# Connector_Sheet.net
KiCad netlist of a schematic drawn in Altium Designer
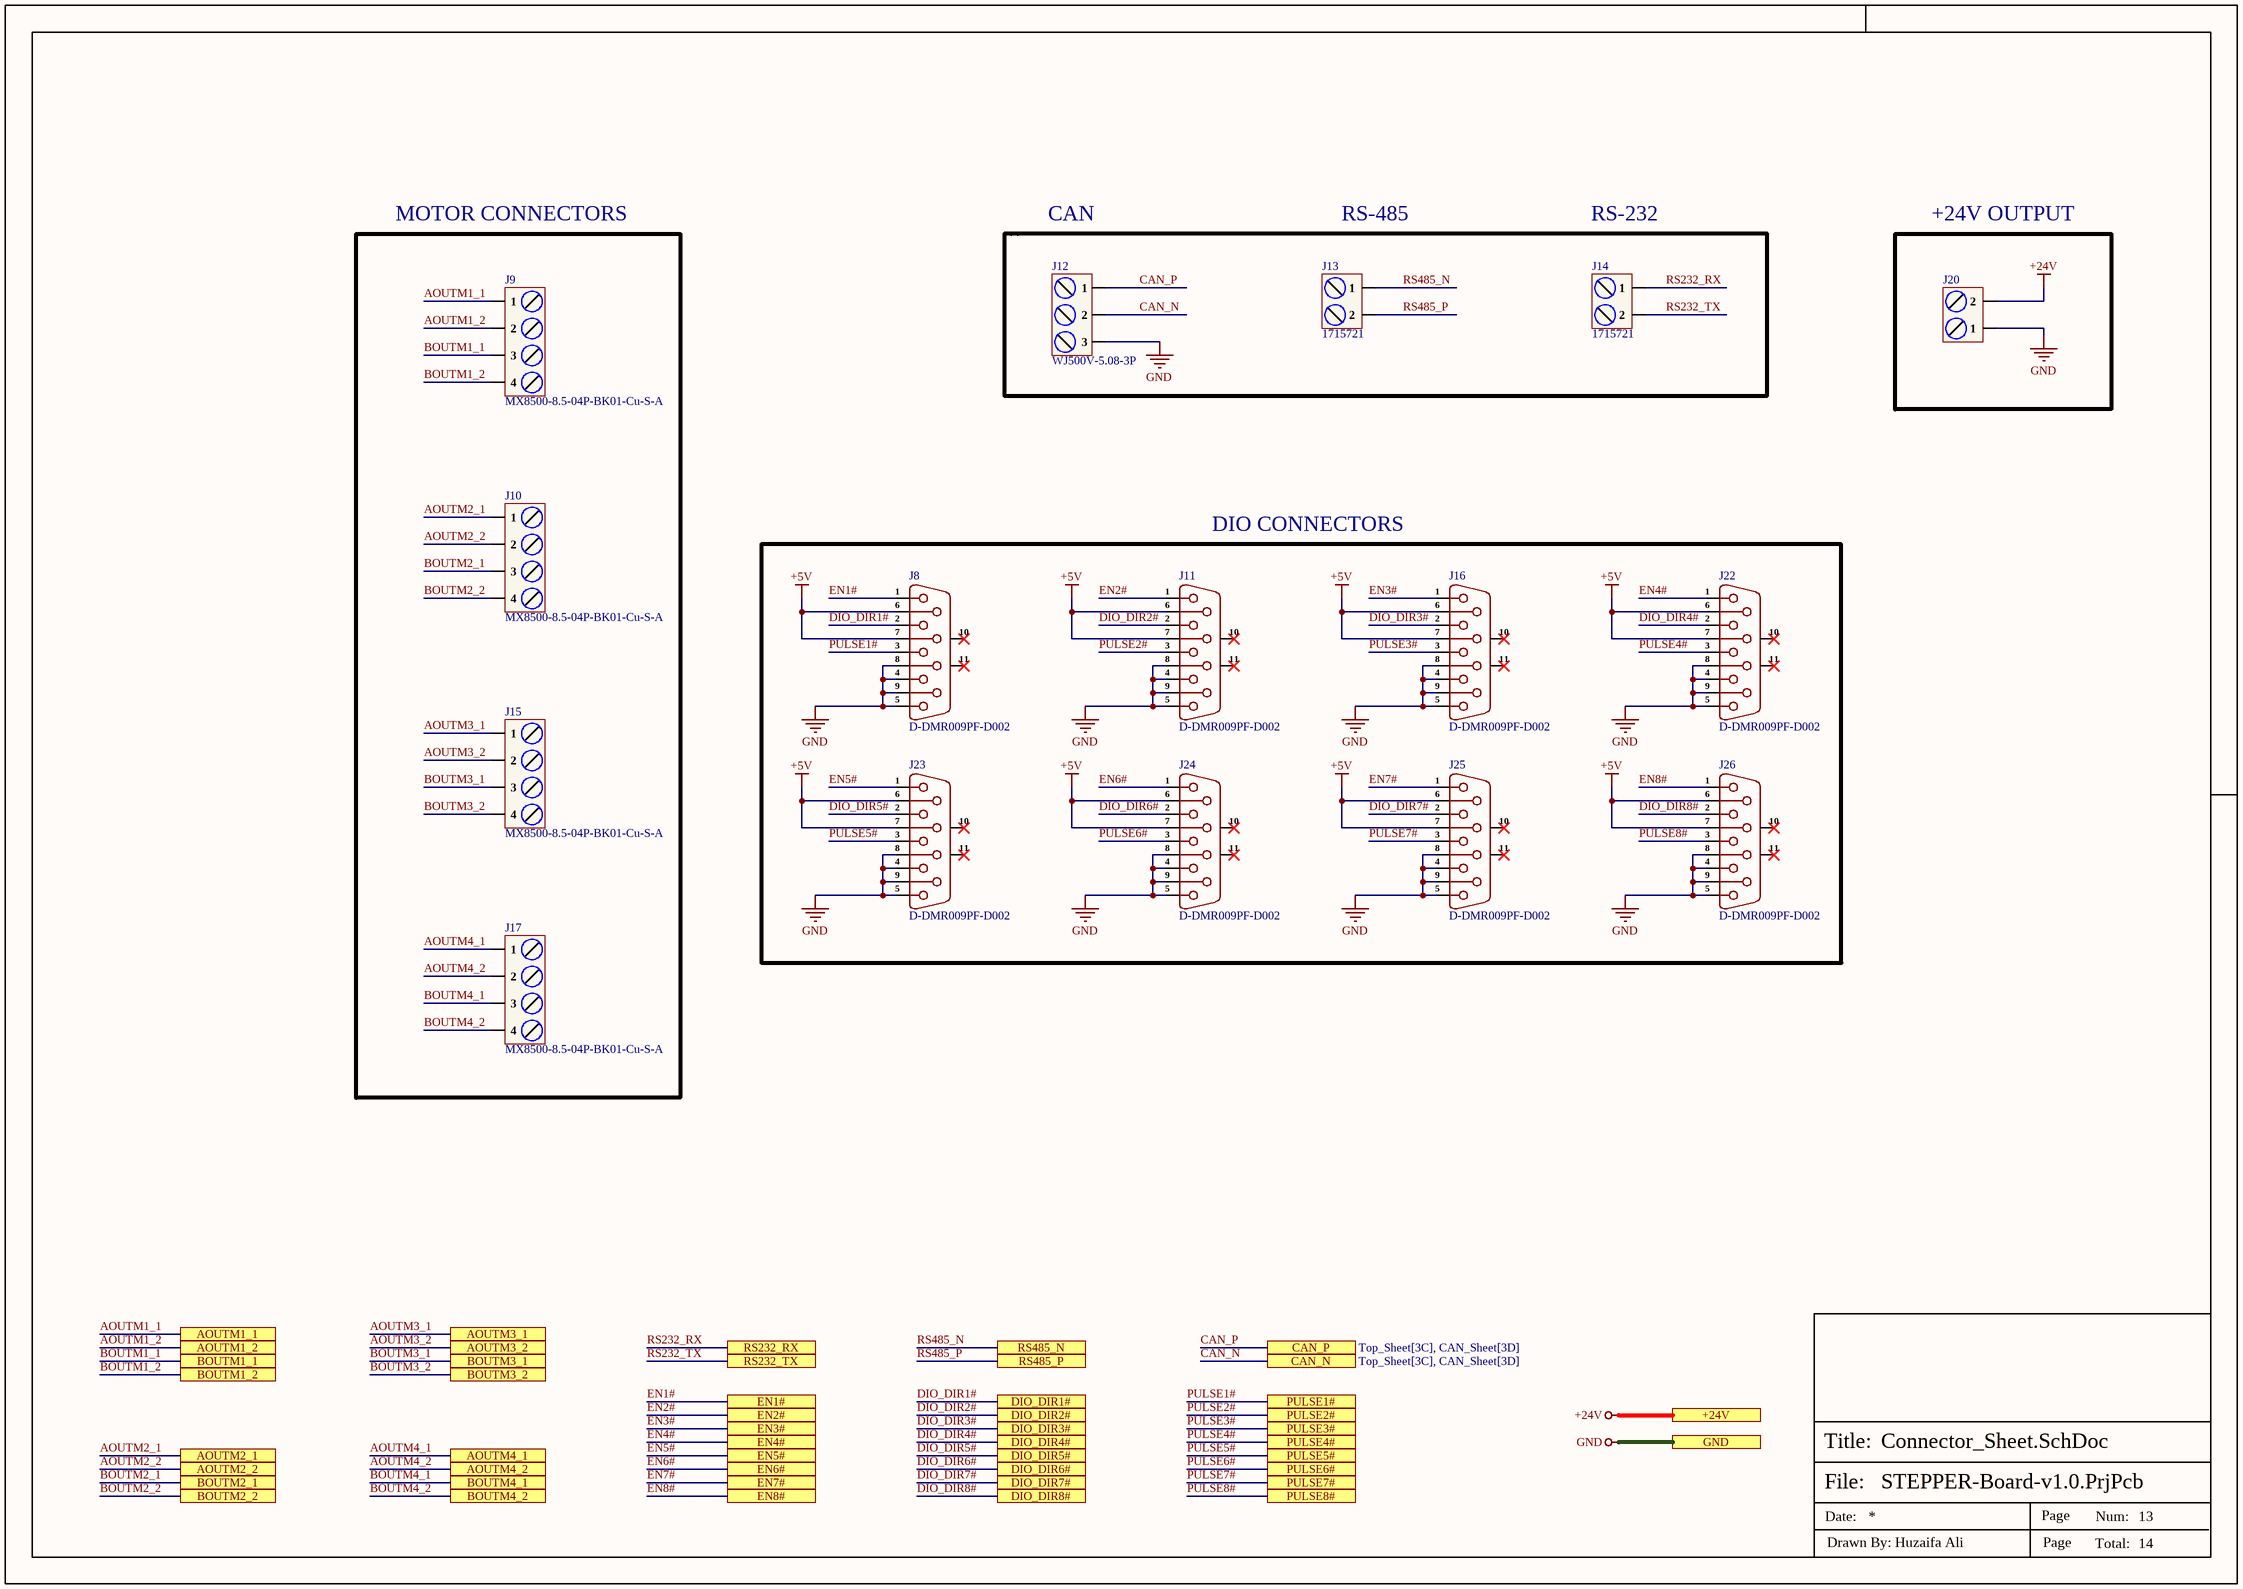
[diagram p0: Connector_Sheet.SchDoc]

(export (version "E")
  (design (tool "Eeschema 10.0.6"))
  (components
    (comp (ref "J8")
      (value "D-DMR009PF-D002")
      (footprint "D-DMR009PF-D002")
      (description "9P Female D-Sub Right-Angle 2 3A -50℃~+105℃ Push-Pull D-Sub / VGA connector ROHS")
      (fields (field (name "MANUFACTURER") "Ckmtw") (field (name "LCSC PART NUMBER") "C141882"))
      (libsource (lib "eSpark Libraries") (part "D-DMR009PF-D002"))
    )
    (comp (ref "J9")
      (value "MX8500-8.5-04P-BK01-Cu-S-A")
      (footprint "MX8500-8.5-04P-BK01-Cu-S-A")
      (fields (field (name "MANUFACTURER") "MAX") (field (name "LCSC PART NUMBER") "C5188508"))
      (libsource (lib "eSpark Libraries") (part "MX8500-8.5-04P-BK01-Cu-S-A"))
    )
    (comp (ref "J10")
      (value "MX8500-8.5-04P-BK01-Cu-S-A")
      (footprint "MX8500-8.5-04P-BK01-Cu-S-A")
      (fields (field (name "MANUFACTURER") "MAX") (field (name "LCSC PART NUMBER") "C5188508"))
      (libsource (lib "eSpark Libraries") (part "MX8500-8.5-04P-BK01-Cu-S-A"))
    )
    (comp (ref "J11")
      (value "D-DMR009PF-D002")
      (footprint "D-DMR009PF-D002")
      (description "9P Female D-Sub Right-Angle 2 3A -50℃~+105℃ Push-Pull D-Sub / VGA connector ROHS")
      (fields (field (name "MANUFACTURER") "Ckmtw") (field (name "LCSC PART NUMBER") "C141882"))
      (libsource (lib "eSpark Libraries") (part "D-DMR009PF-D002"))
    )
    (comp (ref "J12")
      (value "WJ500V-5.08-3P")
      (footprint "WJ500V-5.08-3P")
      (fields (field (name "MANUFACTURER") "Ningbo Kangnex Elec") (field (name "LCSC PART NUMBER") "C72334"))
      (libsource (lib "eSpark Libraries") (part "WJ500V-5.08-3P"))
    )
    (comp (ref "J13")
      (value "1715721")
      (footprint "1715721")
      (description "TERM BLK 2P SIDE ENT 5.08MM PCB")
      (fields (field (name "MANUFACTURER") "Phoenix Contact"))
      (libsource (lib "eSpark Libraries") (part "1715721"))
    )
    (comp (ref "J14")
      (value "1715721")
      (footprint "1715721")
      (description "TERM BLK 2P SIDE ENT 5.08MM PCB")
      (fields (field (name "MANUFACTURER") "Phoenix Contact"))
      (libsource (lib "eSpark Libraries") (part "1715721"))
    )
    (comp (ref "J15")
      (value "MX8500-8.5-04P-BK01-Cu-S-A")
      (footprint "MX8500-8.5-04P-BK01-Cu-S-A")
      (fields (field (name "MANUFACTURER") "MAX") (field (name "LCSC PART NUMBER") "C5188508"))
      (libsource (lib "eSpark Libraries") (part "MX8500-8.5-04P-BK01-Cu-S-A"))
    )
    (comp (ref "J16")
      (value "D-DMR009PF-D002")
      (footprint "D-DMR009PF-D002")
      (description "9P Female D-Sub Right-Angle 2 3A -50℃~+105℃ Push-Pull D-Sub / VGA connector ROHS")
      (fields (field (name "MANUFACTURER") "Ckmtw") (field (name "LCSC PART NUMBER") "C141882"))
      (libsource (lib "eSpark Libraries") (part "D-DMR009PF-D002"))
    )
    (comp (ref "J17")
      (value "MX8500-8.5-04P-BK01-Cu-S-A")
      (footprint "MX8500-8.5-04P-BK01-Cu-S-A")
      (fields (field (name "MANUFACTURER") "MAX") (field (name "LCSC PART NUMBER") "C5188508"))
      (libsource (lib "eSpark Libraries") (part "MX8500-8.5-04P-BK01-Cu-S-A"))
    )
    (comp (ref "J20")
      (value "MXHB9500-9.5-02P-BK01-Cu-S-A")
      (footprint "MXHB9500-9.5-02P-BK01-Cu-S-A")
      (fields (field (name "MANUFACTURER") "MAX") (field (name "LCSC PART NUMBER") "C7542168"))
      (libsource (lib "eSpark Libraries") (part "MXHB9500-9.5-02P-BK01-Cu-S-A"))
    )
    (comp (ref "J22")
      (value "D-DMR009PF-D002")
      (footprint "D-DMR009PF-D002")
      (description "9P Female D-Sub Right-Angle 2 3A -50℃~+105℃ Push-Pull D-Sub / VGA connector ROHS")
      (fields (field (name "MANUFACTURER") "Ckmtw") (field (name "LCSC PART NUMBER") "C141882"))
      (libsource (lib "eSpark Libraries") (part "D-DMR009PF-D002"))
    )
    (comp (ref "J23")
      (value "D-DMR009PF-D002")
      (footprint "D-DMR009PF-D002")
      (description "9P Female D-Sub Right-Angle 2 3A -50℃~+105℃ Push-Pull D-Sub / VGA connector ROHS")
      (fields (field (name "MANUFACTURER") "Ckmtw") (field (name "LCSC PART NUMBER") "C141882"))
      (libsource (lib "eSpark Libraries") (part "D-DMR009PF-D002"))
    )
    (comp (ref "J24")
      (value "D-DMR009PF-D002")
      (footprint "D-DMR009PF-D002")
      (description "9P Female D-Sub Right-Angle 2 3A -50℃~+105℃ Push-Pull D-Sub / VGA connector ROHS")
      (fields (field (name "MANUFACTURER") "Ckmtw") (field (name "LCSC PART NUMBER") "C141882"))
      (libsource (lib "eSpark Libraries") (part "D-DMR009PF-D002"))
    )
    (comp (ref "J25")
      (value "D-DMR009PF-D002")
      (footprint "D-DMR009PF-D002")
      (description "9P Female D-Sub Right-Angle 2 3A -50℃~+105℃ Push-Pull D-Sub / VGA connector ROHS")
      (fields (field (name "MANUFACTURER") "Ckmtw") (field (name "LCSC PART NUMBER") "C141882"))
      (libsource (lib "eSpark Libraries") (part "D-DMR009PF-D002"))
    )
    (comp (ref "J26")
      (value "D-DMR009PF-D002")
      (footprint "D-DMR009PF-D002")
      (description "9P Female D-Sub Right-Angle 2 3A -50℃~+105℃ Push-Pull D-Sub / VGA connector ROHS")
      (fields (field (name "MANUFACTURER") "Ckmtw") (field (name "LCSC PART NUMBER") "C141882"))
      (libsource (lib "eSpark Libraries") (part "D-DMR009PF-D002"))
    )
  )
  (nets
    (net (code "1") (name "+5V") (class "Default")
      (node (ref "J11") (pin "6") (pinfunction "6_6") (pintype "passive"))
      (node (ref "J11") (pin "7") (pinfunction "7_7") (pintype "passive"))
      (node (ref "J16") (pin "6") (pinfunction "6_6") (pintype "passive"))
      (node (ref "J16") (pin "7") (pinfunction "7_7") (pintype "passive"))
      (node (ref "J22") (pin "6") (pinfunction "6_6") (pintype "passive"))
      (node (ref "J22") (pin "7") (pinfunction "7_7") (pintype "passive"))
      (node (ref "J23") (pin "6") (pinfunction "6_6") (pintype "passive"))
      (node (ref "J23") (pin "7") (pinfunction "7_7") (pintype "passive"))
      (node (ref "J24") (pin "6") (pinfunction "6_6") (pintype "passive"))
      (node (ref "J24") (pin "7") (pinfunction "7_7") (pintype "passive"))
      (node (ref "J25") (pin "6") (pinfunction "6_6") (pintype "passive"))
      (node (ref "J25") (pin "7") (pinfunction "7_7") (pintype "passive"))
      (node (ref "J26") (pin "6") (pinfunction "6_6") (pintype "passive"))
      (node (ref "J26") (pin "7") (pinfunction "7_7") (pintype "passive"))
      (node (ref "J8") (pin "6") (pinfunction "6_6") (pintype "passive"))
      (node (ref "J8") (pin "7") (pinfunction "7_7") (pintype "passive"))
    )
    (net (code "2") (name "+24V") (class "Default")
      (node (ref "J20") (pin "2") (pinfunction "2_2") (pintype "passive"))
    )
    (net (code "3") (name "/AOUTM1_1") (class "Default")
      (node (ref "J9") (pin "1") (pinfunction "1_1") (pintype "passive"))
    )
    (net (code "4") (name "/AOUTM1_2") (class "Default")
      (node (ref "J9") (pin "2") (pinfunction "2_2") (pintype "passive"))
    )
    (net (code "5") (name "/AOUTM2_1") (class "Default")
      (node (ref "J10") (pin "1") (pinfunction "1_1") (pintype "passive"))
    )
    (net (code "6") (name "/AOUTM2_2") (class "Default")
      (node (ref "J10") (pin "2") (pinfunction "2_2") (pintype "passive"))
    )
    (net (code "7") (name "/AOUTM3_1") (class "Default")
      (node (ref "J15") (pin "1") (pinfunction "1_1") (pintype "passive"))
    )
    (net (code "8") (name "/AOUTM3_2") (class "Default")
      (node (ref "J15") (pin "2") (pinfunction "2_2") (pintype "passive"))
    )
    (net (code "9") (name "/AOUTM4_1") (class "Default")
      (node (ref "J17") (pin "1") (pinfunction "1_1") (pintype "passive"))
    )
    (net (code "10") (name "/AOUTM4_2") (class "Default")
      (node (ref "J17") (pin "2") (pinfunction "2_2") (pintype "passive"))
    )
    (net (code "11") (name "/BOUTM1_1") (class "Default")
      (node (ref "J9") (pin "3") (pinfunction "3_3") (pintype "passive"))
    )
    (net (code "12") (name "/BOUTM1_2") (class "Default")
      (node (ref "J9") (pin "4") (pinfunction "4_4") (pintype "passive"))
    )
    (net (code "13") (name "/BOUTM2_1") (class "Default")
      (node (ref "J10") (pin "3") (pinfunction "3_3") (pintype "passive"))
    )
    (net (code "14") (name "/BOUTM2_2") (class "Default")
      (node (ref "J10") (pin "4") (pinfunction "4_4") (pintype "passive"))
    )
    (net (code "15") (name "/BOUTM3_1") (class "Default")
      (node (ref "J15") (pin "3") (pinfunction "3_3") (pintype "passive"))
    )
    (net (code "16") (name "/BOUTM3_2") (class "Default")
      (node (ref "J15") (pin "4") (pinfunction "4_4") (pintype "passive"))
    )
    (net (code "17") (name "/BOUTM4_1") (class "Default")
      (node (ref "J17") (pin "3") (pinfunction "3_3") (pintype "passive"))
    )
    (net (code "18") (name "/BOUTM4_2") (class "Default")
      (node (ref "J17") (pin "4") (pinfunction "4_4") (pintype "passive"))
    )
    (net (code "19") (name "/CAN_N") (class "Default")
      (node (ref "J12") (pin "2") (pinfunction "2_2") (pintype "passive"))
    )
    (net (code "20") (name "/CAN_P") (class "Default")
      (node (ref "J12") (pin "1") (pinfunction "1_1") (pintype "passive"))
    )
    (net (code "21") (name "/DIO_DIR1#") (class "Default")
      (node (ref "J8") (pin "2") (pinfunction "2_2") (pintype "passive"))
    )
    (net (code "22") (name "/DIO_DIR2#") (class "Default")
      (node (ref "J11") (pin "2") (pinfunction "2_2") (pintype "passive"))
    )
    (net (code "23") (name "/DIO_DIR3#") (class "Default")
      (node (ref "J16") (pin "2") (pinfunction "2_2") (pintype "passive"))
    )
    (net (code "24") (name "/DIO_DIR4#") (class "Default")
      (node (ref "J22") (pin "2") (pinfunction "2_2") (pintype "passive"))
    )
    (net (code "25") (name "/DIO_DIR5#") (class "Default")
      (node (ref "J23") (pin "2") (pinfunction "2_2") (pintype "passive"))
    )
    (net (code "26") (name "/DIO_DIR6#") (class "Default")
      (node (ref "J24") (pin "2") (pinfunction "2_2") (pintype "passive"))
    )
    (net (code "27") (name "/DIO_DIR7#") (class "Default")
      (node (ref "J25") (pin "2") (pinfunction "2_2") (pintype "passive"))
    )
    (net (code "28") (name "/DIO_DIR8#") (class "Default")
      (node (ref "J26") (pin "2") (pinfunction "2_2") (pintype "passive"))
    )
    (net (code "29") (name "/EN1#") (class "Default")
      (node (ref "J8") (pin "1") (pinfunction "1_1") (pintype "passive"))
    )
    (net (code "30") (name "/EN2#") (class "Default")
      (node (ref "J11") (pin "1") (pinfunction "1_1") (pintype "passive"))
    )
    (net (code "31") (name "/EN3#") (class "Default")
      (node (ref "J16") (pin "1") (pinfunction "1_1") (pintype "passive"))
    )
    (net (code "32") (name "/EN4#") (class "Default")
      (node (ref "J22") (pin "1") (pinfunction "1_1") (pintype "passive"))
    )
    (net (code "33") (name "/EN5#") (class "Default")
      (node (ref "J23") (pin "1") (pinfunction "1_1") (pintype "passive"))
    )
    (net (code "34") (name "/EN6#") (class "Default")
      (node (ref "J24") (pin "1") (pinfunction "1_1") (pintype "passive"))
    )
    (net (code "35") (name "/EN7#") (class "Default")
      (node (ref "J25") (pin "1") (pinfunction "1_1") (pintype "passive"))
    )
    (net (code "36") (name "/EN8#") (class "Default")
      (node (ref "J26") (pin "1") (pinfunction "1_1") (pintype "passive"))
    )
    (net (code "37") (name "/PULSE1#") (class "Default")
      (node (ref "J8") (pin "3") (pinfunction "3_3") (pintype "passive"))
    )
    (net (code "38") (name "/PULSE2#") (class "Default")
      (node (ref "J11") (pin "3") (pinfunction "3_3") (pintype "passive"))
    )
    (net (code "39") (name "/PULSE3#") (class "Default")
      (node (ref "J16") (pin "3") (pinfunction "3_3") (pintype "passive"))
    )
    (net (code "40") (name "/PULSE4#") (class "Default")
      (node (ref "J22") (pin "3") (pinfunction "3_3") (pintype "passive"))
    )
    (net (code "41") (name "/PULSE5#") (class "Default")
      (node (ref "J23") (pin "3") (pinfunction "3_3") (pintype "passive"))
    )
    (net (code "42") (name "/PULSE6#") (class "Default")
      (node (ref "J24") (pin "3") (pinfunction "3_3") (pintype "passive"))
    )
    (net (code "43") (name "/PULSE7#") (class "Default")
      (node (ref "J25") (pin "3") (pinfunction "3_3") (pintype "passive"))
    )
    (net (code "44") (name "/PULSE8#") (class "Default")
      (node (ref "J26") (pin "3") (pinfunction "3_3") (pintype "passive"))
    )
    (net (code "45") (name "/RS232_RX") (class "Default")
      (node (ref "J14") (pin "1") (pinfunction "1_1") (pintype "passive"))
    )
    (net (code "46") (name "/RS232_TX") (class "Default")
      (node (ref "J14") (pin "2") (pinfunction "2_2") (pintype "passive"))
    )
    (net (code "47") (name "/RS485_N") (class "Default")
      (node (ref "J13") (pin "1") (pinfunction "1_1") (pintype "passive"))
    )
    (net (code "48") (name "/RS485_P") (class "Default")
      (node (ref "J13") (pin "2") (pinfunction "2_2") (pintype "passive"))
    )
    (net (code "49") (name "GND") (class "Default")
      (node (ref "J11") (pin "4") (pinfunction "4_4") (pintype "passive"))
      (node (ref "J11") (pin "5") (pinfunction "5_5") (pintype "passive"))
      (node (ref "J11") (pin "8") (pinfunction "8_8") (pintype "passive"))
      (node (ref "J11") (pin "9") (pinfunction "9_9") (pintype "passive"))
      (node (ref "J12") (pin "3") (pinfunction "3_3") (pintype "passive"))
      (node (ref "J16") (pin "4") (pinfunction "4_4") (pintype "passive"))
      (node (ref "J16") (pin "5") (pinfunction "5_5") (pintype "passive"))
      (node (ref "J16") (pin "8") (pinfunction "8_8") (pintype "passive"))
      (node (ref "J16") (pin "9") (pinfunction "9_9") (pintype "passive"))
      (node (ref "J20") (pin "1") (pinfunction "1_1") (pintype "passive"))
      (node (ref "J22") (pin "4") (pinfunction "4_4") (pintype "passive"))
      (node (ref "J22") (pin "5") (pinfunction "5_5") (pintype "passive"))
      (node (ref "J22") (pin "8") (pinfunction "8_8") (pintype "passive"))
      (node (ref "J22") (pin "9") (pinfunction "9_9") (pintype "passive"))
      (node (ref "J23") (pin "4") (pinfunction "4_4") (pintype "passive"))
      (node (ref "J23") (pin "5") (pinfunction "5_5") (pintype "passive"))
      (node (ref "J23") (pin "8") (pinfunction "8_8") (pintype "passive"))
      (node (ref "J23") (pin "9") (pinfunction "9_9") (pintype "passive"))
      (node (ref "J24") (pin "4") (pinfunction "4_4") (pintype "passive"))
      (node (ref "J24") (pin "5") (pinfunction "5_5") (pintype "passive"))
      (node (ref "J24") (pin "8") (pinfunction "8_8") (pintype "passive"))
      (node (ref "J24") (pin "9") (pinfunction "9_9") (pintype "passive"))
      (node (ref "J25") (pin "4") (pinfunction "4_4") (pintype "passive"))
      (node (ref "J25") (pin "5") (pinfunction "5_5") (pintype "passive"))
      (node (ref "J25") (pin "8") (pinfunction "8_8") (pintype "passive"))
      (node (ref "J25") (pin "9") (pinfunction "9_9") (pintype "passive"))
      (node (ref "J26") (pin "4") (pinfunction "4_4") (pintype "passive"))
      (node (ref "J26") (pin "5") (pinfunction "5_5") (pintype "passive"))
      (node (ref "J26") (pin "8") (pinfunction "8_8") (pintype "passive"))
      (node (ref "J26") (pin "9") (pinfunction "9_9") (pintype "passive"))
      (node (ref "J8") (pin "4") (pinfunction "4_4") (pintype "passive"))
      (node (ref "J8") (pin "5") (pinfunction "5_5") (pintype "passive"))
      (node (ref "J8") (pin "8") (pinfunction "8_8") (pintype "passive"))
      (node (ref "J8") (pin "9") (pinfunction "9_9") (pintype "passive"))
    )
    (net (code "50") (name "unconnected-(J8-MH1-Pad10)") (class "Default")
      (node (ref "J8") (pin "10") (pinfunction "MH1_10") (pintype "passive+no_connect"))
    )
    (net (code "51") (name "unconnected-(J8-MH2-Pad11)") (class "Default")
      (node (ref "J8") (pin "11") (pinfunction "MH2_11") (pintype "passive+no_connect"))
    )
    (net (code "52") (name "unconnected-(J11-MH1-Pad10)") (class "Default")
      (node (ref "J11") (pin "10") (pinfunction "MH1_10") (pintype "passive+no_connect"))
    )
    (net (code "53") (name "unconnected-(J11-MH2-Pad11)") (class "Default")
      (node (ref "J11") (pin "11") (pinfunction "MH2_11") (pintype "passive+no_connect"))
    )
    (net (code "54") (name "unconnected-(J16-MH1-Pad10)") (class "Default")
      (node (ref "J16") (pin "10") (pinfunction "MH1_10") (pintype "passive+no_connect"))
    )
    (net (code "55") (name "unconnected-(J16-MH2-Pad11)") (class "Default")
      (node (ref "J16") (pin "11") (pinfunction "MH2_11") (pintype "passive+no_connect"))
    )
    (net (code "56") (name "unconnected-(J22-MH1-Pad10)") (class "Default")
      (node (ref "J22") (pin "10") (pinfunction "MH1_10") (pintype "passive+no_connect"))
    )
    (net (code "57") (name "unconnected-(J22-MH2-Pad11)") (class "Default")
      (node (ref "J22") (pin "11") (pinfunction "MH2_11") (pintype "passive+no_connect"))
    )
    (net (code "58") (name "unconnected-(J23-MH1-Pad10)") (class "Default")
      (node (ref "J23") (pin "10") (pinfunction "MH1_10") (pintype "passive+no_connect"))
    )
    (net (code "59") (name "unconnected-(J23-MH2-Pad11)") (class "Default")
      (node (ref "J23") (pin "11") (pinfunction "MH2_11") (pintype "passive+no_connect"))
    )
    (net (code "60") (name "unconnected-(J24-MH1-Pad10)") (class "Default")
      (node (ref "J24") (pin "10") (pinfunction "MH1_10") (pintype "passive+no_connect"))
    )
    (net (code "61") (name "unconnected-(J24-MH2-Pad11)") (class "Default")
      (node (ref "J24") (pin "11") (pinfunction "MH2_11") (pintype "passive+no_connect"))
    )
    (net (code "62") (name "unconnected-(J25-MH1-Pad10)") (class "Default")
      (node (ref "J25") (pin "10") (pinfunction "MH1_10") (pintype "passive+no_connect"))
    )
    (net (code "63") (name "unconnected-(J25-MH2-Pad11)") (class "Default")
      (node (ref "J25") (pin "11") (pinfunction "MH2_11") (pintype "passive+no_connect"))
    )
    (net (code "64") (name "unconnected-(J26-MH1-Pad10)") (class "Default")
      (node (ref "J26") (pin "10") (pinfunction "MH1_10") (pintype "passive+no_connect"))
    )
    (net (code "65") (name "unconnected-(J26-MH2-Pad11)") (class "Default")
      (node (ref "J26") (pin "11") (pinfunction "MH2_11") (pintype "passive+no_connect"))
    )
  )
)
